# TK513_Limiter.net
KiCad netlist of a schematic drawn in Altium Designer
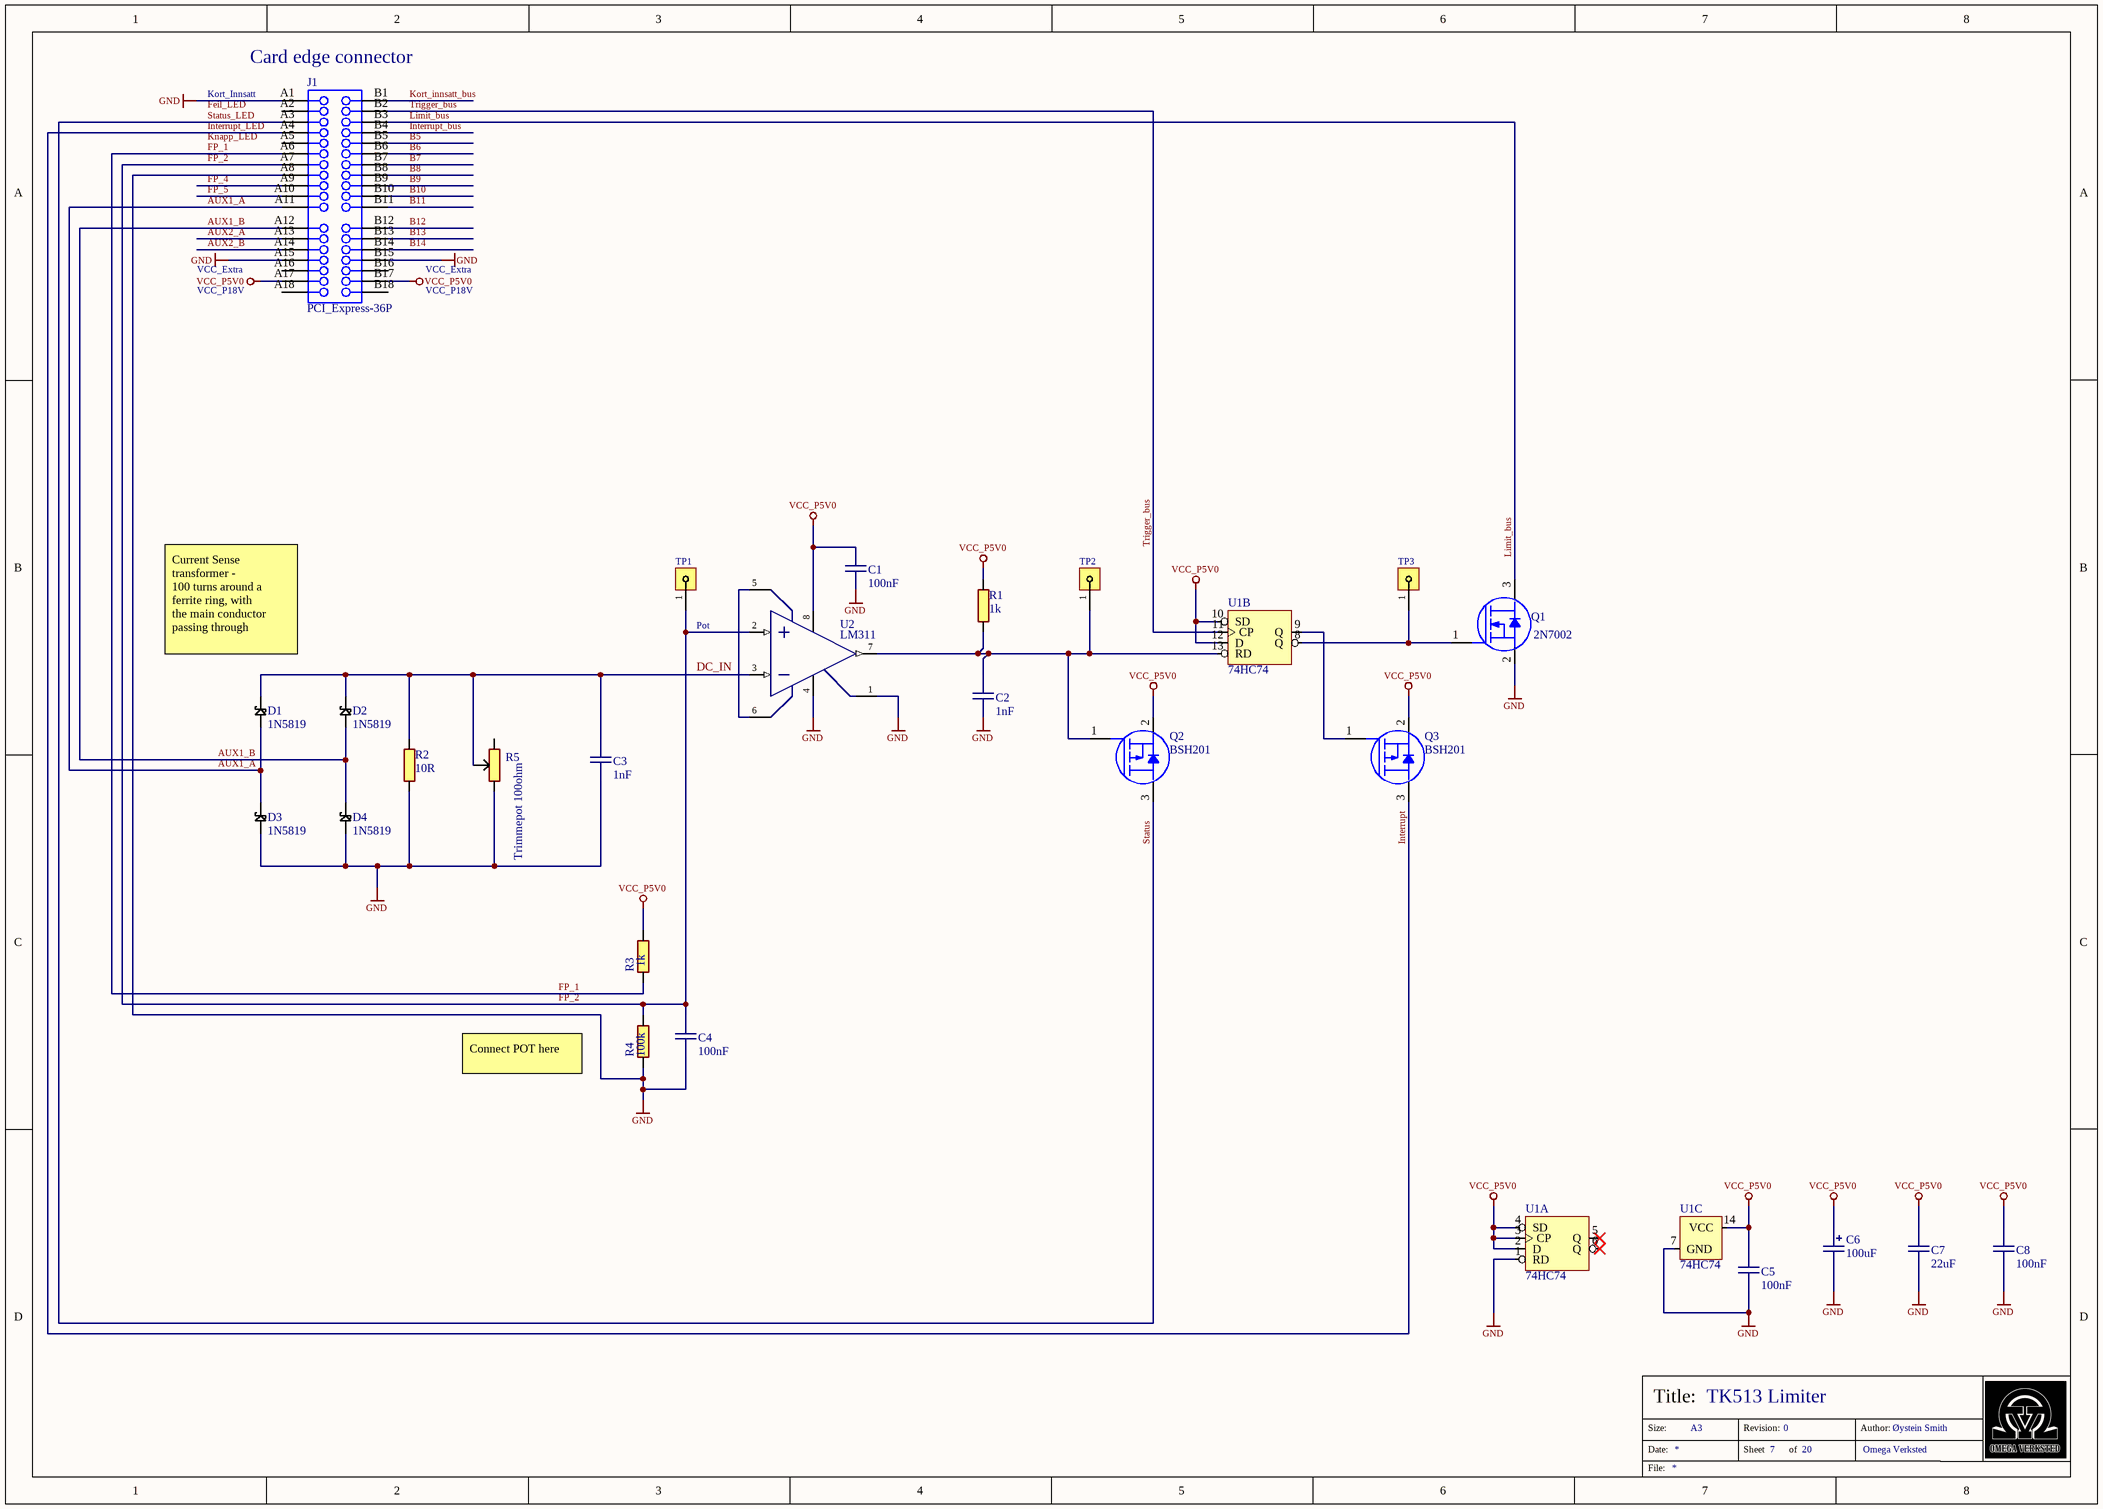
[diagram p0: TK513_Limiter.SchDoc]

(export (version "E")
  (design (tool "Eeschema 10.0.6"))
  (components
    (comp (ref "C1")
      (value "100nF")
      (footprint "CAPC0603(1608)55_N")
      (description "X7R 50V 5%")
      (libsource (lib "OVLib_64") (part "CAP"))
    )
    (comp (ref "C2")
      (value "1nF")
      (footprint "CAPC0603(1608)55_N")
      (description "X7R 50V 5%")
      (libsource (lib "OVLib_64") (part "CAP"))
    )
    (comp (ref "C3")
      (value "1nF")
      (footprint "CAPC0603(1608)55_N")
      (description "X7R 50V 5%")
      (libsource (lib "OVLib_64") (part "CAP"))
    )
    (comp (ref "C4")
      (value "100nF")
      (footprint "CAPC0603(1608)55_N")
      (description "X7R 50V 5%")
      (libsource (lib "OVLib_64") (part "CAP"))
    )
    (comp (ref "C5")
      (value "100nF")
      (footprint "CAPC0603(1608)55_N")
      (description "X7R 50V 5%")
      (libsource (lib "OVLib_64") (part "CAP"))
    )
    (comp (ref "C6")
      (value "100uF")
      (footprint "CAPPR25D06H11")
      (description "25V 2.5mm pitch")
      (libsource (lib "OVLib_64") (part "POLCAP"))
    )
    (comp (ref "C7")
      (value "22uF")
      (footprint "CAPC1206(3216)170_N")
      (description "10V 10% Tantalum")
      (libsource (lib "OVLib_64") (part "CAP"))
    )
    (comp (ref "C8")
      (value "100nF")
      (footprint "CAPC0603(1608)55_N")
      (description "X7R 50V 5%")
      (libsource (lib "OVLib_64") (part "CAP"))
    )
    (comp (ref "D1")
      (value "1N5819")
      (footprint "DO-41")
      (description "Schottkydiode, 1A, 40V")
      (libsource (lib "OVLib_64") (part "SchottkyDiode"))
    )
    (comp (ref "D2")
      (value "1N5819")
      (footprint "DO-41")
      (description "Schottkydiode, 1A, 40V")
      (libsource (lib "OVLib_64") (part "SchottkyDiode"))
    )
    (comp (ref "D3")
      (value "1N5819")
      (footprint "DO-41")
      (description "Schottkydiode, 1A, 40V")
      (libsource (lib "OVLib_64") (part "SchottkyDiode"))
    )
    (comp (ref "D4")
      (value "1N5819")
      (footprint "DO-41")
      (description "Schottkydiode, 1A, 40V")
      (libsource (lib "OVLib_64") (part "SchottkyDiode"))
    )
    (comp (ref "J1")
      (value "PCI_Express-36P")
      (footprint "PCIeX1-GF-2D-1000-1K-O36")
      (description "PCI express PCB kortkankonnektor")
      (libsource (lib "OVLib_64") (part "PCI_Express-36P"))
    )
    (comp (ref "Q1")
      (value "2N7002")
      (footprint "SOT323_N")
      (description "N-Channel MOSFET 300mA")
      (libsource (lib "OVLib_64") (part "MOSFET_N_GSD"))
    )
    (comp (ref "Q2")
      (value "BSH201")
      (footprint "SOT23-3_N")
      (description "P-Channel MOSFET 300mA")
      (libsource (lib "OVLib_64") (part "MOSFET_P_GSD"))
    )
    (comp (ref "Q3")
      (value "BSH201")
      (footprint "SOT23-3_N")
      (description "P-Channel MOSFET 300mA")
      (libsource (lib "OVLib_64") (part "MOSFET_P_GSD"))
    )
    (comp (ref "R1")
      (value "1k")
      (footprint "RESC0603(1608)_N")
      (description "0.1W 1% Thick film resistor")
      (libsource (lib "OVLib_64") (part "Resistor2"))
    )
    (comp (ref "R2")
      (value "10R")
      (footprint "RESC0603(1608)_N")
      (description "0.1W 1% Thick film resistor")
      (libsource (lib "OVLib_64") (part "Resistor2"))
    )
    (comp (ref "R3")
      (value "1k")
      (footprint "RESC0603(1608)_N")
      (description "0.1W 1% Thick film resistor")
      (libsource (lib "OVLib_64") (part "Resistor2"))
    )
    (comp (ref "R4")
      (value "100k")
      (footprint "RESC0603(1608)_N")
      (description "0.1W 1% Thick film resistor")
      (libsource (lib "OVLib_64") (part "Resistor2"))
    )
    (comp (ref "R5")
      (value "Trimmepot 100ohm")
      (footprint "TRIMPOT_3006P")
      (description "15 turn, horizontal")
      (libsource (lib "OVLib_64") (part "Potmeter"))
    )
    (comp (ref "TP1")
      (value "Header1x1")
      (footprint "HDRV1W64P254_1X1_254X254X900B")
      (description "2,54mm pitch")
      (libsource (lib "OVLib_64") (part "Header1x1"))
    )
    (comp (ref "TP2")
      (value "Header1x1")
      (footprint "HDRV1W64P254_1X1_254X254X900B")
      (description "2,54mm pitch")
      (libsource (lib "OVLib_64") (part "Header1x1"))
    )
    (comp (ref "TP3")
      (value "Header1x1")
      (footprint "HDRV1W64P254_1X1_254X254X900B")
      (description "2,54mm pitch")
      (libsource (lib "OVLib_64") (part "Header1x1"))
    )
    (comp (ref "U1")
      (value "74HC74")
      (footprint "SOIC-14")
      (description "Dual D flip flop")
      (libsource (lib "OVLib_64") (part "2XD-Flip-Flop"))
    )
    (comp (ref "U2")
      (value "LM311")
      (footprint "SOIC-8-WIDE")
      (description "Comparator, High Speed")
      (libsource (lib "OVLib_64") (part "Comparator_Complex"))
    )
  )
  (nets
    (net (code "1") (name "/AUX1_A") (class "Default")
      (node (ref "D1") (pin "1") (pinfunction "A_1") (pintype "passive"))
      (node (ref "D3") (pin "2") (pinfunction "K_2") (pintype "passive"))
      (node (ref "J1") (pin "A11") (pinfunction "A11_A11") (pintype "passive"))
    )
    (net (code "2") (name "/AUX1_B") (class "Default")
      (node (ref "D2") (pin "1") (pinfunction "A_1") (pintype "passive"))
      (node (ref "D4") (pin "2") (pinfunction "K_2") (pintype "passive"))
      (node (ref "J1") (pin "A12") (pinfunction "A12_A12") (pintype "passive"))
    )
    (net (code "3") (name "/AUX2_A") (class "Default")
      (node (ref "J1") (pin "A13") (pinfunction "A13_A13") (pintype "passive"))
    )
    (net (code "4") (name "/AUX2_B") (class "Default")
      (node (ref "J1") (pin "A14") (pinfunction "A14_A14") (pintype "passive"))
    )
    (net (code "5") (name "/B5") (class "Default")
      (node (ref "J1") (pin "B5") (pinfunction "B5_B5") (pintype "passive"))
    )
    (net (code "6") (name "/B6") (class "Default")
      (node (ref "J1") (pin "B6") (pinfunction "B6_B6") (pintype "passive"))
    )
    (net (code "7") (name "/B7") (class "Default")
      (node (ref "J1") (pin "B7") (pinfunction "B7_B7") (pintype "passive"))
    )
    (net (code "8") (name "/B8") (class "Default")
      (node (ref "J1") (pin "B8") (pinfunction "B8_B8") (pintype "passive"))
    )
    (net (code "9") (name "/B9") (class "Default")
      (node (ref "J1") (pin "B9") (pinfunction "B9_B9") (pintype "passive"))
    )
    (net (code "10") (name "/B10") (class "Default")
      (node (ref "J1") (pin "B10") (pinfunction "B10_B10") (pintype "passive"))
    )
    (net (code "11") (name "/B11") (class "Default")
      (node (ref "J1") (pin "B11") (pinfunction "B11_B11") (pintype "passive"))
    )
    (net (code "12") (name "/B12") (class "Default")
      (node (ref "J1") (pin "B12") (pinfunction "B12_B12") (pintype "passive"))
    )
    (net (code "13") (name "/B13") (class "Default")
      (node (ref "J1") (pin "B13") (pinfunction "B13_B13") (pintype "passive"))
    )
    (net (code "14") (name "/B14") (class "Default")
      (node (ref "J1") (pin "B14") (pinfunction "B14_B14") (pintype "passive"))
    )
    (net (code "15") (name "/DC_IN") (class "Default")
      (node (ref "C3") (pin "2") (pinfunction "2_2") (pintype "passive"))
      (node (ref "D1") (pin "2") (pinfunction "K_2") (pintype "passive"))
      (node (ref "D2") (pin "2") (pinfunction "K_2") (pintype "passive"))
      (node (ref "R2") (pin "1") (pinfunction "1_1") (pintype "passive"))
      (node (ref "R5") (pin "2") (pinfunction "2_2") (pintype "passive"))
      (node (ref "U2") (pin "3") (pinfunction "IN-_3") (pintype "input"))
    )
    (net (code "16") (name "/FP_1") (class "Default")
      (node (ref "J1") (pin "A6") (pinfunction "A6_A6") (pintype "passive"))
      (node (ref "R3") (pin "2") (pinfunction "2_2") (pintype "passive"))
    )
    (net (code "17") (name "/FP_2") (class "Default")
      (node (ref "C4") (pin "2") (pinfunction "2_2") (pintype "passive"))
      (node (ref "J1") (pin "A7") (pinfunction "A7_A7") (pintype "passive"))
      (node (ref "R4") (pin "1") (pinfunction "1_1") (pintype "passive"))
      (node (ref "TP1") (pin "1") (pinfunction "1_1") (pintype "passive"))
      (node (ref "U2") (pin "2") (pinfunction "IN+_2") (pintype "input"))
    )
    (net (code "18") (name "/FP_4") (class "Default")
      (node (ref "J1") (pin "A9") (pinfunction "A9_A9") (pintype "passive"))
    )
    (net (code "19") (name "/FP_5") (class "Default")
      (node (ref "J1") (pin "A10") (pinfunction "A10_A10") (pintype "passive"))
    )
    (net (code "21") (name "/Interrupt") (class "Default")
      (node (ref "J1") (pin "A4") (pinfunction "A4_A4") (pintype "passive"))
      (node (ref "Q3") (pin "3") (pinfunction "Drain_3") (pintype "passive"))
    )
    (net (code "22") (name "/Interrupt_bus") (class "Default")
      (node (ref "J1") (pin "B4") (pinfunction "B4_B4") (pintype "passive"))
    )
    (net (code "24") (name "/Kort_innsatt_bus") (class "Default")
      (node (ref "J1") (pin "B1") (pinfunction "B1_B1") (pintype "passive"))
    )
    (net (code "25") (name "/Limit_bus") (class "Default")
      (node (ref "J1") (pin "B3") (pinfunction "B3_B3") (pintype "passive"))
      (node (ref "Q1") (pin "3") (pinfunction "Drain_3") (pintype "passive"))
    )
    (net (code "26") (name "/Status") (class "Default")
      (node (ref "J1") (pin "A3") (pinfunction "A3_A3") (pintype "passive"))
      (node (ref "Q2") (pin "3") (pinfunction "Drain_3") (pintype "passive"))
    )
    (net (code "27") (name "/Trigger_bus") (class "Default")
      (node (ref "J1") (pin "B2") (pinfunction "B2_B2") (pintype "passive"))
      (node (ref "U1") (pin "11") (pinfunction "CP_11") (pintype "passive"))
    )
    (net (code "28") (name "GND") (class "Default")
      (node (ref "C1") (pin "1") (pinfunction "1_1") (pintype "passive"))
      (node (ref "C2") (pin "1") (pinfunction "1_1") (pintype "passive"))
      (node (ref "C3") (pin "1") (pinfunction "1_1") (pintype "passive"))
      (node (ref "C4") (pin "1") (pinfunction "1_1") (pintype "passive"))
      (node (ref "C5") (pin "1") (pinfunction "1_1") (pintype "passive"))
      (node (ref "C6") (pin "1") (pinfunction "1_1") (pintype "passive"))
      (node (ref "C7") (pin "1") (pinfunction "1_1") (pintype "passive"))
      (node (ref "C8") (pin "1") (pinfunction "1_1") (pintype "passive"))
      (node (ref "D3") (pin "1") (pinfunction "A_1") (pintype "passive"))
      (node (ref "D4") (pin "1") (pinfunction "A_1") (pintype "passive"))
      (node (ref "J1") (pin "A1") (pinfunction "A1_A1") (pintype "passive"))
      (node (ref "J1") (pin "A15") (pinfunction "A15_A15") (pintype "passive"))
      (node (ref "J1") (pin "A8") (pinfunction "A8_A8") (pintype "passive"))
      (node (ref "J1") (pin "B15") (pinfunction "B15_B15") (pintype "passive"))
      (node (ref "Q1") (pin "2") (pinfunction "Source_2") (pintype "passive"))
      (node (ref "R2") (pin "2") (pinfunction "2_2") (pintype "passive"))
      (node (ref "R4") (pin "2") (pinfunction "2_2") (pintype "passive"))
      (node (ref "R5") (pin "1") (pinfunction "1_1") (pintype "passive"))
      (node (ref "U1") (pin "1") (pinfunction "RD_1") (pintype "passive"))
      (node (ref "U1") (pin "7") (pinfunction "GND_7") (pintype "passive"))
      (node (ref "U2") (pin "1") (pinfunction "GND_1") (pintype "power_in"))
      (node (ref "U2") (pin "4") (pinfunction "V-_4") (pintype "power_in"))
    )
    (net (code "29") (name "Net-(Q1-Gate)") (class "Default")
      (node (ref "Q1") (pin "1") (pinfunction "Gate_1") (pintype "passive"))
      (node (ref "TP3") (pin "1") (pinfunction "1_1") (pintype "passive"))
      (node (ref "U1") (pin "8") (pinfunction "Q_8") (pintype "passive"))
    )
    (net (code "30") (name "Net-(Q2-Gate)") (class "Default")
      (node (ref "C2") (pin "2") (pinfunction "2_2") (pintype "passive"))
      (node (ref "Q2") (pin "1") (pinfunction "Gate_1") (pintype "passive"))
      (node (ref "R1") (pin "2") (pinfunction "2_2") (pintype "passive"))
      (node (ref "TP2") (pin "1") (pinfunction "1_1") (pintype "passive"))
      (node (ref "U1") (pin "13") (pinfunction "RD_13") (pintype "passive"))
      (node (ref "U2") (pin "7") (pinfunction "OUT_7") (pintype "output"))
    )
    (net (code "31") (name "Net-(Q3-Gate)") (class "Default")
      (node (ref "Q3") (pin "1") (pinfunction "Gate_1") (pintype "passive"))
      (node (ref "U1") (pin "9") (pinfunction "Q_9") (pintype "passive"))
    )
    (net (code "32") (name "Net-(U2-BAL)") (class "Default")
      (node (ref "U2") (pin "5") (pinfunction "BAL_5") (pintype "passive"))
      (node (ref "U2") (pin "6") (pinfunction "BAL/STB_6") (pintype "passive"))
    )
    (net (code "33") (name "VCC_P5V0") (class "Default")
      (node (ref "C1") (pin "2") (pinfunction "2_2") (pintype "passive"))
      (node (ref "C5") (pin "2") (pinfunction "2_2") (pintype "passive"))
      (node (ref "C6") (pin "2") (pinfunction "2_2") (pintype "passive"))
      (node (ref "C7") (pin "2") (pinfunction "2_2") (pintype "passive"))
      (node (ref "C8") (pin "2") (pinfunction "2_2") (pintype "passive"))
      (node (ref "J1") (pin "A17") (pinfunction "A17_A17") (pintype "passive"))
      (node (ref "J1") (pin "B17") (pinfunction "B17_B17") (pintype "passive"))
      (node (ref "Q2") (pin "2") (pinfunction "Source_2") (pintype "passive"))
      (node (ref "Q3") (pin "2") (pinfunction "Source_2") (pintype "passive"))
      (node (ref "R1") (pin "1") (pinfunction "1_1") (pintype "passive"))
      (node (ref "R3") (pin "1") (pinfunction "1_1") (pintype "passive"))
      (node (ref "U1") (pin "10") (pinfunction "SD_10") (pintype "passive"))
      (node (ref "U1") (pin "12") (pinfunction "D_12") (pintype "passive"))
      (node (ref "U1") (pin "14") (pinfunction "VCC_14") (pintype "passive"))
      (node (ref "U1") (pin "2") (pinfunction "D_2") (pintype "passive"))
      (node (ref "U1") (pin "3") (pinfunction "CP_3") (pintype "passive"))
      (node (ref "U1") (pin "4") (pinfunction "SD_4") (pintype "passive"))
      (node (ref "U2") (pin "8") (pinfunction "V+_8") (pintype "power_in"))
    )
    (net (code "34") (name "unconnected-(J1-PadA2)") (class "Default")
      (node (ref "J1") (pin "A2") (pinfunction "A2_A2") (pintype "passive"))
    )
    (net (code "35") (name "unconnected-(J1-PadA5)") (class "Default")
      (node (ref "J1") (pin "A5") (pinfunction "A5_A5") (pintype "passive"))
    )
    (net (code "36") (name "unconnected-(J1-PadA16)") (class "Default")
      (node (ref "J1") (pin "A16") (pinfunction "A16_A16") (pintype "passive"))
    )
    (net (code "37") (name "unconnected-(J1-PadA18)") (class "Default")
      (node (ref "J1") (pin "A18") (pinfunction "A18_A18") (pintype "passive"))
    )
    (net (code "38") (name "unconnected-(J1-PadB16)") (class "Default")
      (node (ref "J1") (pin "B16") (pinfunction "B16_B16") (pintype "passive"))
    )
    (net (code "39") (name "unconnected-(J1-PadB18)") (class "Default")
      (node (ref "J1") (pin "B18") (pinfunction "B18_B18") (pintype "passive"))
    )
    (net (code "40") (name "unconnected-(R5-Pad3)") (class "Default")
      (node (ref "R5") (pin "3") (pinfunction "3_3") (pintype "passive"))
    )
    (net (code "41") (name "unconnected-(U1A-Q-Pad5)") (class "Default")
      (node (ref "U1") (pin "5") (pinfunction "Q_5") (pintype "passive+no_connect"))
    )
    (net (code "42") (name "unconnected-(U1A-Q-Pad6)") (class "Default")
      (node (ref "U1") (pin "6") (pinfunction "Q_6") (pintype "passive+no_connect"))
    )
  )
)
